# Hardware_lichtsturing_schema.net
KiCad netlist of a schematic drawn in EAGLE
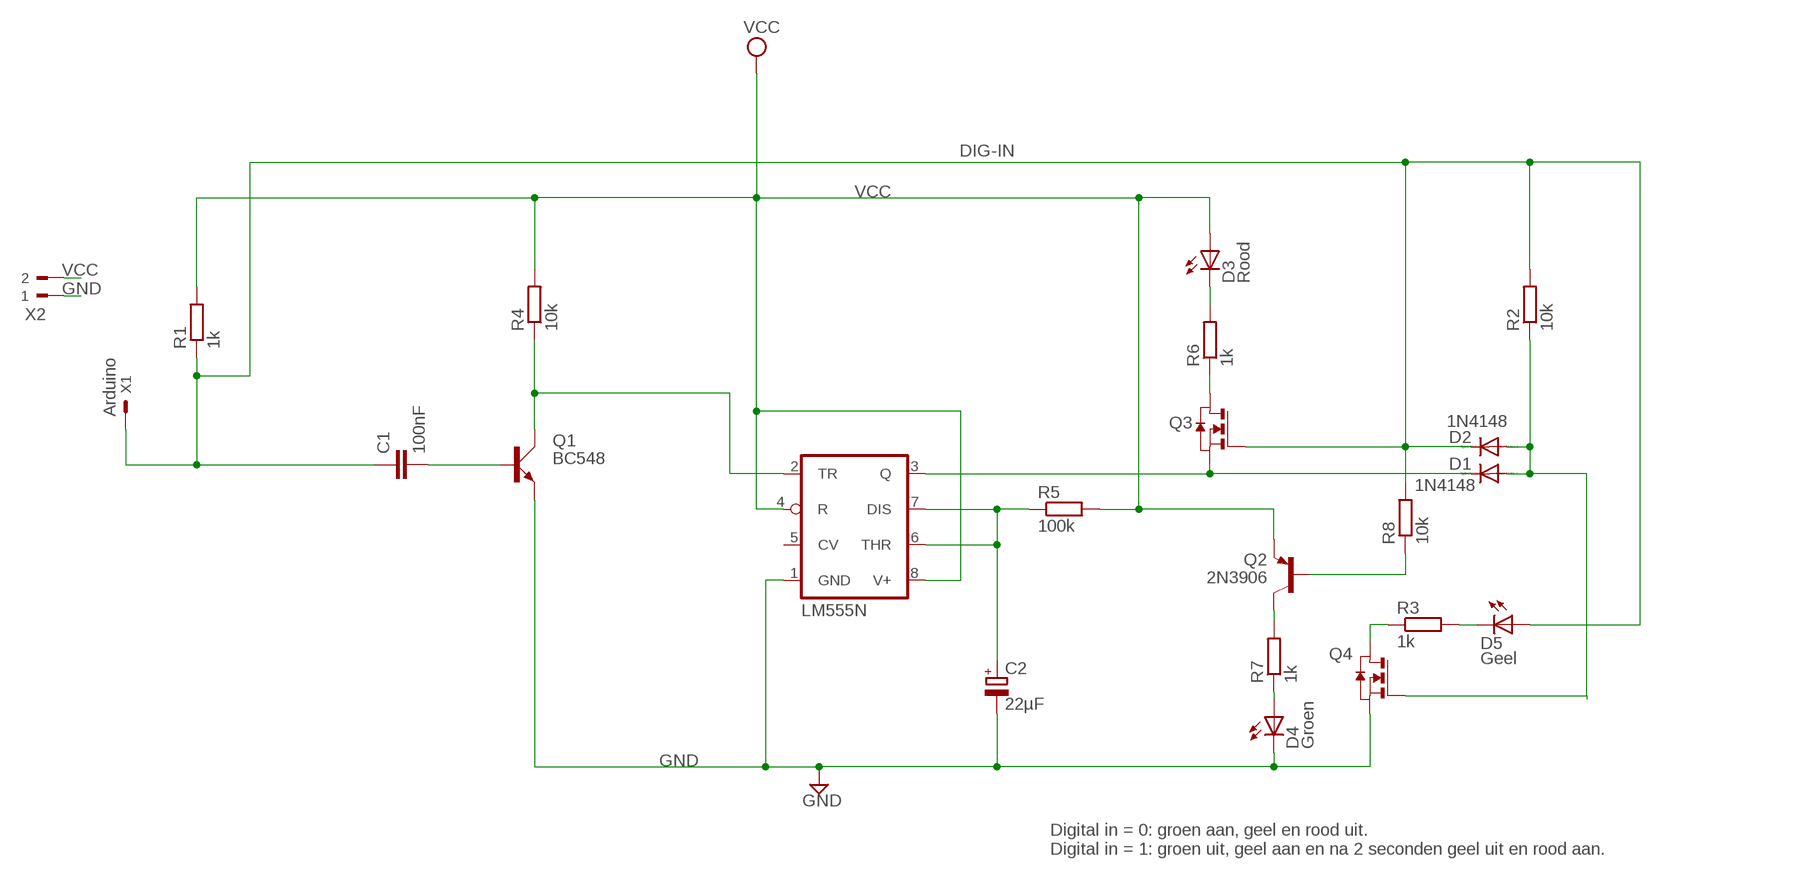
[diagram p0: schematic, sheet 1]

(export (version "E")
  (design (tool "Eeschema 10.0.6"))
  (components
    (comp (ref "C1")
      (value "100nF")
      (footprint "eagle-import:C050-024X044")
      (libsource (lib "eagle-import") (part "CAPACITOR"))
    )
    (comp (ref "C2")
      (value "22µF")
      (footprint "eagle-import:E3,5-8")
      (libsource (lib "eagle-import") (part "ELCO"))
    )
    (comp (ref "D1")
      (value "1N4148")
      (footprint "eagle-import:DO35-7")
      (libsource (lib "eagle-import") (part "1N4148DO35-7"))
    )
    (comp (ref "D2")
      (value "1N4148")
      (footprint "eagle-import:DO35-7")
      (libsource (lib "eagle-import") (part "1N4148DO35-7"))
    )
    (comp (ref "D3")
      (value "Rood")
      (footprint "eagle-import:LED3MM")
      (fields (field (name "MF") "VISHAY SEMICONDUCTOR"))
      (libsource (lib "eagle-import") (part "TLLY4400"))
    )
    (comp (ref "D4")
      (value "Groen")
      (footprint "eagle-import:LED3MM")
      (fields (field (name "MF") "VISHAY SEMICONDUCTOR"))
      (libsource (lib "eagle-import") (part "TLLY4400"))
    )
    (comp (ref "D5")
      (value "Geel")
      (footprint "eagle-import:LED3MM")
      (fields (field (name "MF") "VISHAY SEMICONDUCTOR"))
      (libsource (lib "eagle-import") (part "TLLY4400"))
    )
    (comp (ref "IC1")
      (value "LM555N")
      (footprint "eagle-import:DIL08")
      (libsource (lib "eagle-import") (part "555NLM"))
    )
    (comp (ref "Q1")
      (value "BC548")
      (footprint "eagle-import:TO220AV")
      (libsource (lib "eagle-import") (part "TIP41C"))
    )
    (comp (ref "Q2")
      (value "2N3906")
      (footprint "eagle-import:TO92")
      (libsource (lib "eagle-import") (part "BC307"))
    )
    (comp (ref "Q3")
      (value "NMOSE3L")
      (footprint "eagle-import:E3LINE")
      (libsource (lib "eagle-import") (part "NMOSE3L"))
    )
    (comp (ref "Q4")
      (value "NMOSE3L")
      (footprint "eagle-import:E3LINE")
      (libsource (lib "eagle-import") (part "NMOSE3L"))
    )
    (comp (ref "R1")
      (value "1k")
      (footprint "eagle-import:RDH_15")
      (libsource (lib "eagle-import") (part "RESISTOR"))
    )
    (comp (ref "R2")
      (value "10k")
      (footprint "eagle-import:RDH_15")
      (libsource (lib "eagle-import") (part "RESISTOR"))
    )
    (comp (ref "R3")
      (value "1k")
      (footprint "eagle-import:RDH_15")
      (libsource (lib "eagle-import") (part "RESISTOR"))
    )
    (comp (ref "R4")
      (value "10k")
      (footprint "eagle-import:RDH_15")
      (libsource (lib "eagle-import") (part "RESISTOR"))
    )
    (comp (ref "R5")
      (value "100k")
      (footprint "eagle-import:RDH_15")
      (libsource (lib "eagle-import") (part "RESISTOR"))
    )
    (comp (ref "R6")
      (value "1k")
      (footprint "eagle-import:RDH_15")
      (libsource (lib "eagle-import") (part "RESISTOR"))
    )
    (comp (ref "R7")
      (value "1k")
      (footprint "eagle-import:RDH_15")
      (libsource (lib "eagle-import") (part "RESISTOR"))
    )
    (comp (ref "R8")
      (value "10k")
      (footprint "eagle-import:RDH_15")
      (libsource (lib "eagle-import") (part "RESISTOR"))
    )
    (comp (ref "X1")
      (value "Arduino")
      (footprint "eagle-import:332-02")
      (libsource (lib "eagle-import") (part "332-02"))
    )
    (comp (ref "X2")
      (value "90-2")
      (footprint "eagle-import:90-2")
      (libsource (lib "eagle-import") (part "90-2"))
    )
  )
  (nets
    (net (code "1") (name "/DIG-IN") (class "Default")
      (node (ref "C1") (pin "1") (pinfunction "1_1") (pintype "passive"))
      (node (ref "D2") (pin "C") (pinfunction "C_C") (pintype "passive"))
      (node (ref "D5") (pin "A") (pinfunction "A_A") (pintype "passive"))
      (node (ref "Q3") (pin "2") (pinfunction "G_2") (pintype "passive"))
      (node (ref "R1") (pin "1") (pinfunction "1_1") (pintype "passive"))
      (node (ref "R2") (pin "2") (pinfunction "2_2") (pintype "passive"))
      (node (ref "R8") (pin "2") (pinfunction "2_2") (pintype "passive"))
      (node (ref "X1") (pin "1") (pinfunction "S_1") (pintype "passive"))
    )
    (net (code "2") (name "GND") (class "Default")
      (node (ref "C2") (pin "-") (pinfunction "-_-") (pintype "passive"))
      (node (ref "D4") (pin "K") (pinfunction "C_K") (pintype "passive"))
      (node (ref "IC1") (pin "1") (pinfunction "GND_1") (pintype "power_in"))
      (node (ref "Q1") (pin "E") (pinfunction "E_E") (pintype "passive"))
      (node (ref "Q4") (pin "3") (pinfunction "S_3") (pintype "passive"))
      (node (ref "X2") (pin "1") (pinfunction "1_1") (pintype "passive"))
    )
    (net (code "3") (name "Net-(C1-Pad2)") (class "Default")
      (node (ref "C1") (pin "2") (pinfunction "2_2") (pintype "passive"))
      (node (ref "Q1") (pin "B") (pinfunction "B_B") (pintype "passive"))
    )
    (net (code "4") (name "Net-(D3-C)") (class "Default")
      (node (ref "D3") (pin "K") (pinfunction "C_K") (pintype "passive"))
      (node (ref "R6") (pin "2") (pinfunction "2_2") (pintype "passive"))
    )
    (net (code "5") (name "Net-(D4-PadA)") (class "Default")
      (node (ref "D4") (pin "A") (pinfunction "A_A") (pintype "passive"))
      (node (ref "R7") (pin "1") (pinfunction "1_1") (pintype "passive"))
    )
    (net (code "6") (name "Net-(D5-C)") (class "Default")
      (node (ref "D5") (pin "K") (pinfunction "C_K") (pintype "passive"))
      (node (ref "R3") (pin "2") (pinfunction "2_2") (pintype "passive"))
    )
    (net (code "7") (name "Net-(IC1-DIS)") (class "Default")
      (node (ref "C2") (pin "+") (pinfunction "+_+") (pintype "passive"))
      (node (ref "IC1") (pin "6") (pinfunction "THR_6") (pintype "input"))
      (node (ref "IC1") (pin "7") (pinfunction "DIS_7") (pintype "input"))
      (node (ref "R5") (pin "1") (pinfunction "1_1") (pintype "passive"))
    )
    (net (code "8") (name "Net-(IC1-Q)") (class "Default")
      (node (ref "D1") (pin "C") (pinfunction "C_C") (pintype "passive"))
      (node (ref "IC1") (pin "3") (pinfunction "Q_3") (pintype "output"))
      (node (ref "Q3") (pin "3") (pinfunction "S_3") (pintype "passive"))
    )
    (net (code "9") (name "Net-(IC1-TR)") (class "Default")
      (node (ref "IC1") (pin "2") (pinfunction "TR_2") (pintype "input"))
      (node (ref "Q1") (pin "C") (pinfunction "C_C") (pintype "passive"))
      (node (ref "R4") (pin "1") (pinfunction "1_1") (pintype "passive"))
    )
    (net (code "10") (name "Net-(Q2-B)") (class "Default")
      (node (ref "Q2") (pin "2") (pinfunction "B_2") (pintype "passive"))
      (node (ref "R8") (pin "1") (pinfunction "1_1") (pintype "passive"))
    )
    (net (code "11") (name "Net-(Q2-C)") (class "Default")
      (node (ref "Q2") (pin "3") (pinfunction "C_3") (pintype "passive"))
      (node (ref "R7") (pin "2") (pinfunction "2_2") (pintype "passive"))
    )
    (net (code "12") (name "Net-(Q3-D)") (class "Default")
      (node (ref "Q3") (pin "1") (pinfunction "D_1") (pintype "passive"))
      (node (ref "R6") (pin "1") (pinfunction "1_1") (pintype "passive"))
    )
    (net (code "13") (name "Net-(Q4-D)") (class "Default")
      (node (ref "Q4") (pin "1") (pinfunction "D_1") (pintype "passive"))
      (node (ref "R3") (pin "1") (pinfunction "1_1") (pintype "passive"))
    )
    (net (code "14") (name "Net-(Q4-G)") (class "Default")
      (node (ref "D1") (pin "A") (pinfunction "A_A") (pintype "passive"))
      (node (ref "D2") (pin "A") (pinfunction "A_A") (pintype "passive"))
      (node (ref "Q4") (pin "2") (pinfunction "G_2") (pintype "passive"))
      (node (ref "R2") (pin "1") (pinfunction "1_1") (pintype "passive"))
    )
    (net (code "15") (name "VCC") (class "Default")
      (node (ref "D3") (pin "A") (pinfunction "A_A") (pintype "passive"))
      (node (ref "IC1") (pin "4") (pinfunction "R_4") (pintype "input"))
      (node (ref "IC1") (pin "8") (pinfunction "V+_8") (pintype "power_in"))
      (node (ref "Q2") (pin "1") (pinfunction "E_1") (pintype "passive"))
      (node (ref "R1") (pin "2") (pinfunction "2_2") (pintype "passive"))
      (node (ref "R4") (pin "2") (pinfunction "2_2") (pintype "passive"))
      (node (ref "R5") (pin "2") (pinfunction "2_2") (pintype "passive"))
      (node (ref "X2") (pin "2") (pinfunction "2_2") (pintype "passive"))
    )
    (net (code "16") (name "unconnected-(IC1-CV-Pad5)") (class "Default")
      (node (ref "IC1") (pin "5") (pinfunction "CV_5") (pintype "input"))
    )
  )
)
